# L293D.net
KiCad netlist of a schematic drawn in Altium Designer
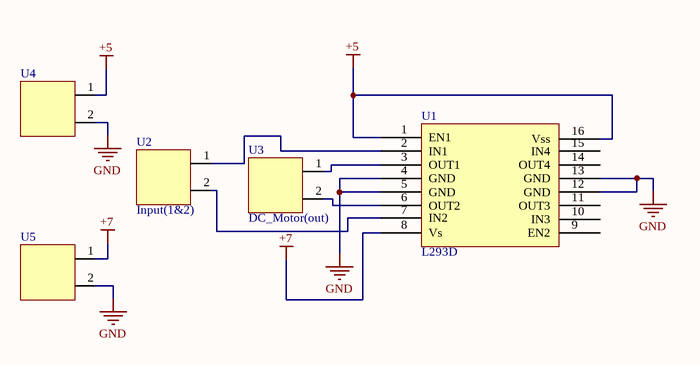
[diagram p0: L293D.SchDoc]

(export (version "E")
  (design (tool "Eeschema 10.0.6"))
  (components
    (comp (ref "U1")
      (value "L293D")
      (footprint "L293D - duplicate")
      (fields (field (name "MANUFACTURER") "Texas Instrument"))
      (libsource (lib "PCB2_session") (part "L293D_IC"))
    )
    (comp (ref "U2")
      (value "Input(1&2)")
      (footprint "Terminal_Block")
      (libsource (lib "PCB2_session") (part "Terminal_Block"))
    )
    (comp (ref "U3")
      (value "DC_Motor(out)")
      (footprint "Terminal_Block")
      (libsource (lib "PCB2_session") (part "Terminal_Block"))
    )
    (comp (ref "U4")
      (value "Terminal_Block")
      (footprint "Terminal_Block")
      (libsource (lib "PCB2_session") (part "Terminal_Block"))
    )
    (comp (ref "U5")
      (value "Terminal_Block")
      (footprint "Terminal_Block")
      (libsource (lib "PCB2_session") (part "Terminal_Block"))
    )
  )
  (nets
    (net (code "1") (name "+5") (class "Default")
      (node (ref "U1") (pin "1") (pinfunction "EN1_1") (pintype "passive"))
      (node (ref "U1") (pin "16") (pinfunction "Vss_16") (pintype "passive"))
      (node (ref "U4") (pin "1") (pintype "passive"))
    )
    (net (code "2") (name "+7") (class "Default")
      (node (ref "U1") (pin "8") (pinfunction "Vs_8") (pintype "passive"))
      (node (ref "U5") (pin "1") (pintype "passive"))
    )
    (net (code "3") (name "GND") (class "Default")
      (node (ref "U1") (pin "12") (pinfunction "GND_12") (pintype "passive"))
      (node (ref "U1") (pin "13") (pinfunction "GND_13") (pintype "passive"))
      (node (ref "U1") (pin "4") (pinfunction "GND_4") (pintype "passive"))
      (node (ref "U1") (pin "5") (pinfunction "GND_5") (pintype "passive"))
      (node (ref "U4") (pin "2") (pintype "passive"))
      (node (ref "U5") (pin "2") (pintype "passive"))
    )
    (net (code "4") (name "Net-(U1-IN1)") (class "Default")
      (node (ref "U1") (pin "2") (pinfunction "IN1_2") (pintype "passive"))
      (node (ref "U2") (pin "1") (pintype "passive"))
    )
    (net (code "5") (name "Net-(U1-IN2)") (class "Default")
      (node (ref "U1") (pin "7") (pinfunction "IN2_7") (pintype "passive"))
      (node (ref "U2") (pin "2") (pintype "passive"))
    )
    (net (code "6") (name "Net-(U1-OUT1)") (class "Default")
      (node (ref "U1") (pin "3") (pinfunction "OUT1_3") (pintype "passive"))
      (node (ref "U3") (pin "1") (pintype "passive"))
    )
    (net (code "7") (name "Net-(U1-OUT2)") (class "Default")
      (node (ref "U1") (pin "6") (pinfunction "OUT2_6") (pintype "passive"))
      (node (ref "U3") (pin "2") (pintype "passive"))
    )
    (net (code "8") (name "unconnected-(U1-EN2-Pad9)") (class "Default")
      (node (ref "U1") (pin "9") (pinfunction "EN2_9") (pintype "passive"))
    )
    (net (code "9") (name "unconnected-(U1-IN3-Pad10)") (class "Default")
      (node (ref "U1") (pin "10") (pinfunction "IN3_10") (pintype "passive"))
    )
    (net (code "10") (name "unconnected-(U1-IN4-Pad15)") (class "Default")
      (node (ref "U1") (pin "15") (pinfunction "IN4_15") (pintype "passive"))
    )
    (net (code "11") (name "unconnected-(U1-OUT3-Pad11)") (class "Default")
      (node (ref "U1") (pin "11") (pinfunction "OUT3_11") (pintype "passive"))
    )
    (net (code "12") (name "unconnected-(U1-OUT4-Pad14)") (class "Default")
      (node (ref "U1") (pin "14") (pinfunction "OUT4_14") (pintype "passive"))
    )
  )
)
